# modem.net
KiCad netlist of a schematic drawn in Altium Designer
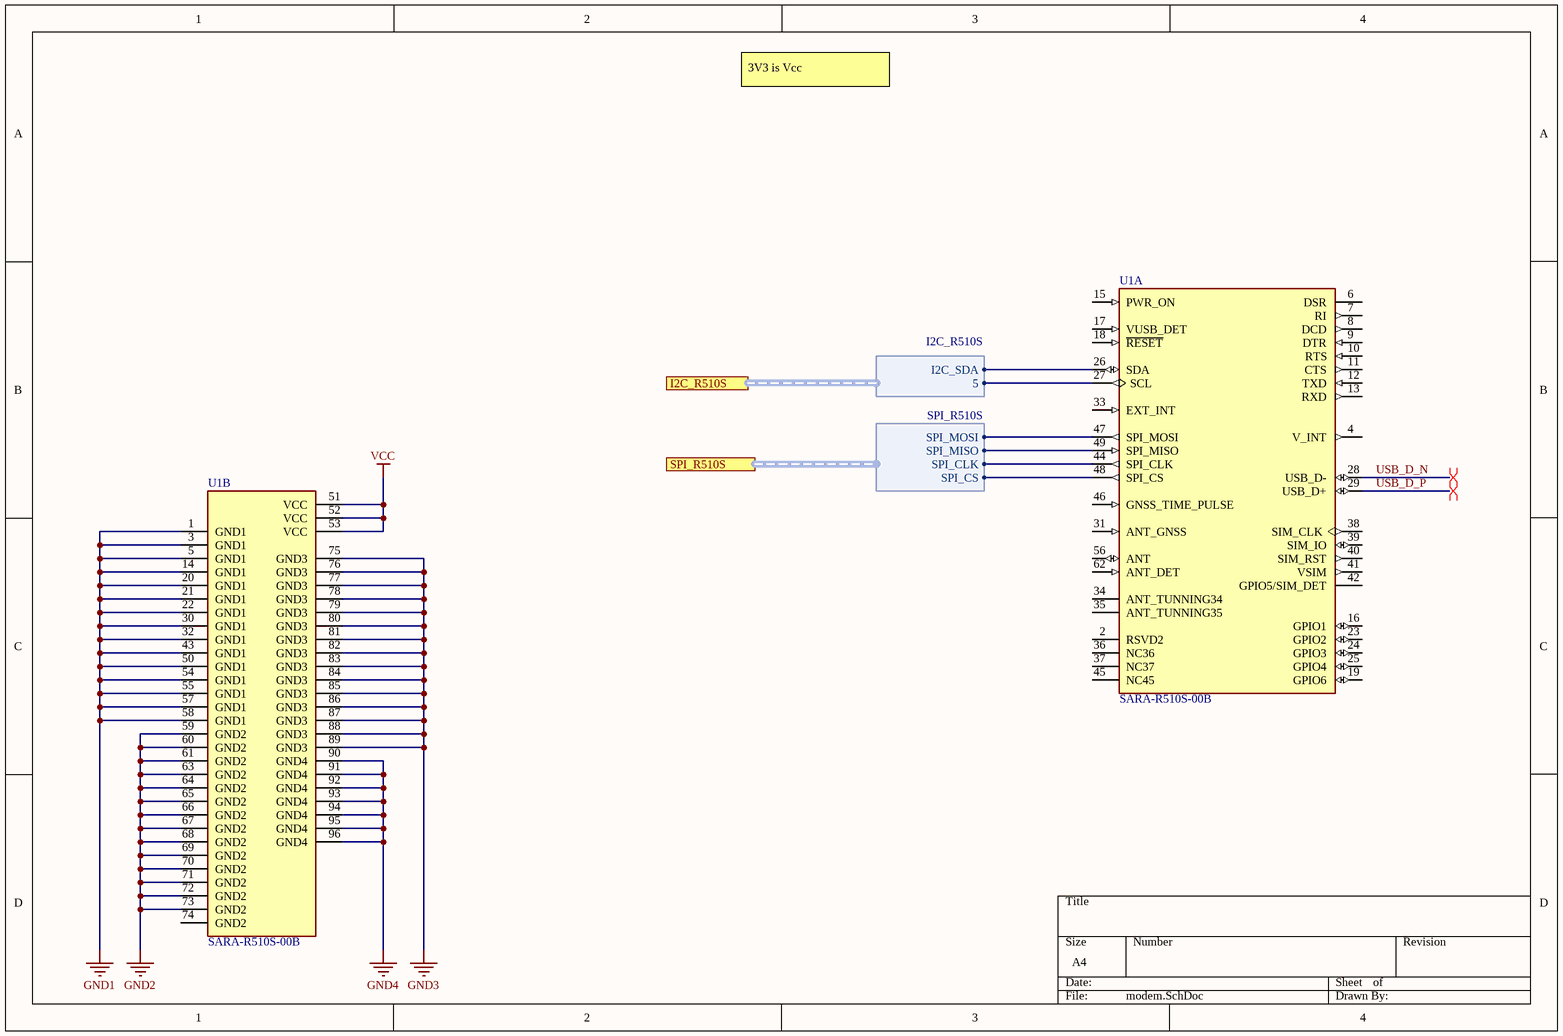
[diagram p0: modem.SchDoc]

(export (version "E")
  (design (tool "Eeschema 10.0.6"))
  (components
    (comp (ref "U1")
      (value "SARA-R510S-00B")
      (footprint "MODULE_SARA-R510S-00B - CORRECTED")
      (fields (field (name "MF") "U-Blox"))
      (libsource (lib "SARA-R510S-00B") (part "SARA-R510S-00B"))
    )
  )
  (nets
    (net (code "3") (name "/5") (class "Default")
      (node (ref "U1") (pin "27") (pinfunction "SCL_27") (pintype "output"))
    )
    (net (code "4") (name "/I2C_SDA") (class "Default")
      (node (ref "U1") (pin "26") (pinfunction "SDA_26") (pintype "bidirectional"))
    )
    (net (code "5") (name "/SPI_CLK") (class "Default")
      (node (ref "U1") (pin "44") (pinfunction "SPI_CLK_44") (pintype "output"))
    )
    (net (code "6") (name "/SPI_CS") (class "Default")
      (node (ref "U1") (pin "48") (pinfunction "SPI_CS_48") (pintype "output"))
    )
    (net (code "7") (name "/SPI_MISO") (class "Default")
      (node (ref "U1") (pin "49") (pinfunction "SPI_MISO_49") (pintype "input"))
    )
    (net (code "8") (name "/SPI_MOSI") (class "Default")
      (node (ref "U1") (pin "47") (pinfunction "SPI_MOSI_47") (pintype "output"))
    )
    (net (code "9") (name "/USB_D_N") (class "Default")
      (node (ref "U1") (pin "28") (pinfunction "USB_D-_28") (pintype "bidirectional"))
    )
    (net (code "10") (name "/USB_D_P") (class "Default")
      (node (ref "U1") (pin "29") (pinfunction "USB_D+_29") (pintype "bidirectional"))
    )
    (net (code "13") (name "GND1") (class "Default")
      (node (ref "U1") (pin "1") (pinfunction "GND1_1") (pintype "power_in"))
      (node (ref "U1") (pin "14") (pinfunction "GND1_14") (pintype "power_in"))
      (node (ref "U1") (pin "20") (pinfunction "GND1_20") (pintype "power_in"))
      (node (ref "U1") (pin "21") (pinfunction "GND1_21") (pintype "power_in"))
      (node (ref "U1") (pin "22") (pinfunction "GND1_22") (pintype "power_in"))
      (node (ref "U1") (pin "3") (pinfunction "GND1_3") (pintype "power_in"))
      (node (ref "U1") (pin "30") (pinfunction "GND1_30") (pintype "power_in"))
      (node (ref "U1") (pin "32") (pinfunction "GND1_32") (pintype "power_in"))
      (node (ref "U1") (pin "43") (pinfunction "GND1_43") (pintype "power_in"))
      (node (ref "U1") (pin "5") (pinfunction "GND1_5") (pintype "power_in"))
      (node (ref "U1") (pin "50") (pinfunction "GND1_50") (pintype "power_in"))
      (node (ref "U1") (pin "54") (pinfunction "GND1_54") (pintype "power_in"))
      (node (ref "U1") (pin "55") (pinfunction "GND1_55") (pintype "power_in"))
      (node (ref "U1") (pin "57") (pinfunction "GND1_57") (pintype "power_in"))
      (node (ref "U1") (pin "58") (pinfunction "GND1_58") (pintype "power_in"))
    )
    (net (code "14") (name "GND2") (class "Default")
      (node (ref "U1") (pin "59") (pinfunction "GND2_59") (pintype "power_in"))
      (node (ref "U1") (pin "60") (pinfunction "GND2_60") (pintype "power_in"))
      (node (ref "U1") (pin "61") (pinfunction "GND2_61") (pintype "power_in"))
      (node (ref "U1") (pin "63") (pinfunction "GND2_63") (pintype "power_in"))
      (node (ref "U1") (pin "64") (pinfunction "GND2_64") (pintype "power_in"))
      (node (ref "U1") (pin "65") (pinfunction "GND2_65") (pintype "power_in"))
      (node (ref "U1") (pin "66") (pinfunction "GND2_66") (pintype "power_in"))
      (node (ref "U1") (pin "67") (pinfunction "GND2_67") (pintype "power_in"))
      (node (ref "U1") (pin "68") (pinfunction "GND2_68") (pintype "power_in"))
      (node (ref "U1") (pin "69") (pinfunction "GND2_69") (pintype "power_in"))
      (node (ref "U1") (pin "70") (pinfunction "GND2_70") (pintype "power_in"))
      (node (ref "U1") (pin "71") (pinfunction "GND2_71") (pintype "power_in"))
      (node (ref "U1") (pin "72") (pinfunction "GND2_72") (pintype "power_in"))
      (node (ref "U1") (pin "73") (pinfunction "GND2_73") (pintype "power_in"))
    )
    (net (code "15") (name "GND3") (class "Default")
      (node (ref "U1") (pin "75") (pinfunction "GND3_75") (pintype "power_in"))
      (node (ref "U1") (pin "76") (pinfunction "GND3_76") (pintype "power_in"))
      (node (ref "U1") (pin "77") (pinfunction "GND3_77") (pintype "power_in"))
      (node (ref "U1") (pin "78") (pinfunction "GND3_78") (pintype "power_in"))
      (node (ref "U1") (pin "79") (pinfunction "GND3_79") (pintype "power_in"))
      (node (ref "U1") (pin "80") (pinfunction "GND3_80") (pintype "power_in"))
      (node (ref "U1") (pin "81") (pinfunction "GND3_81") (pintype "power_in"))
      (node (ref "U1") (pin "82") (pinfunction "GND3_82") (pintype "power_in"))
      (node (ref "U1") (pin "83") (pinfunction "GND3_83") (pintype "power_in"))
      (node (ref "U1") (pin "84") (pinfunction "GND3_84") (pintype "power_in"))
      (node (ref "U1") (pin "85") (pinfunction "GND3_85") (pintype "power_in"))
      (node (ref "U1") (pin "86") (pinfunction "GND3_86") (pintype "power_in"))
      (node (ref "U1") (pin "87") (pinfunction "GND3_87") (pintype "power_in"))
      (node (ref "U1") (pin "88") (pinfunction "GND3_88") (pintype "power_in"))
      (node (ref "U1") (pin "89") (pinfunction "GND3_89") (pintype "power_in"))
    )
    (net (code "16") (name "GND4") (class "Default")
      (node (ref "U1") (pin "90") (pinfunction "GND4_90") (pintype "power_in"))
      (node (ref "U1") (pin "91") (pinfunction "GND4_91") (pintype "power_in"))
      (node (ref "U1") (pin "92") (pinfunction "GND4_92") (pintype "power_in"))
      (node (ref "U1") (pin "93") (pinfunction "GND4_93") (pintype "power_in"))
      (node (ref "U1") (pin "94") (pinfunction "GND4_94") (pintype "power_in"))
      (node (ref "U1") (pin "95") (pinfunction "GND4_95") (pintype "power_in"))
      (node (ref "U1") (pin "96") (pinfunction "GND4_96") (pintype "power_in"))
    )
    (net (code "17") (name "VCC") (class "Default")
      (node (ref "U1") (pin "51") (pinfunction "VCC_51") (pintype "power_in"))
      (node (ref "U1") (pin "52") (pinfunction "VCC_52") (pintype "power_in"))
      (node (ref "U1") (pin "53") (pinfunction "VCC_53") (pintype "power_in"))
    )
    (net (code "18") (name "unconnected-(U1A-ANT-Pad56)") (class "Default")
      (node (ref "U1") (pin "56") (pinfunction "ANT_56") (pintype "bidirectional"))
    )
    (net (code "19") (name "unconnected-(U1A-ANT_DET-Pad62)") (class "Default")
      (node (ref "U1") (pin "62") (pinfunction "ANT_DET_62") (pintype "input"))
    )
    (net (code "20") (name "unconnected-(U1A-ANT_GNSS-Pad31)") (class "Default")
      (node (ref "U1") (pin "31") (pinfunction "ANT_GNSS_31") (pintype "input"))
    )
    (net (code "21") (name "unconnected-(U1A-ANT_TUNNING34-Pad34)") (class "Default")
      (node (ref "U1") (pin "34") (pinfunction "ANT_TUNNING34_34") (pintype "passive"))
    )
    (net (code "22") (name "unconnected-(U1A-ANT_TUNNING35-Pad35)") (class "Default")
      (node (ref "U1") (pin "35") (pinfunction "ANT_TUNNING35_35") (pintype "passive"))
    )
    (net (code "23") (name "unconnected-(U1A-CTS-Pad11)") (class "Default")
      (node (ref "U1") (pin "11") (pinfunction "CTS_11") (pintype "output"))
    )
    (net (code "24") (name "unconnected-(U1A-DCD-Pad8)") (class "Default")
      (node (ref "U1") (pin "8") (pinfunction "DCD_8") (pintype "output"))
    )
    (net (code "25") (name "unconnected-(U1A-DSR-Pad6)") (class "Default")
      (node (ref "U1") (pin "6") (pinfunction "DSR_6") (pintype "passive"))
    )
    (net (code "26") (name "unconnected-(U1A-DTR-Pad9)") (class "Default")
      (node (ref "U1") (pin "9") (pinfunction "DTR_9") (pintype "input"))
    )
    (net (code "27") (name "unconnected-(U1A-EXT_INT-Pad33)") (class "Default")
      (node (ref "U1") (pin "33") (pinfunction "EXT_INT_33") (pintype "input"))
    )
    (net (code "28") (name "unconnected-(U1A-GNSS_TIME_PULSE-Pad46)") (class "Default")
      (node (ref "U1") (pin "46") (pinfunction "GNSS_TIME_PULSE_46") (pintype "input"))
    )
    (net (code "29") (name "unconnected-(U1A-GPIO1-Pad16)") (class "Default")
      (node (ref "U1") (pin "16") (pinfunction "GPIO1_16") (pintype "bidirectional"))
    )
    (net (code "30") (name "unconnected-(U1A-GPIO2-Pad23)") (class "Default")
      (node (ref "U1") (pin "23") (pinfunction "GPIO2_23") (pintype "bidirectional"))
    )
    (net (code "31") (name "unconnected-(U1A-GPIO3-Pad24)") (class "Default")
      (node (ref "U1") (pin "24") (pinfunction "GPIO3_24") (pintype "bidirectional"))
    )
    (net (code "32") (name "unconnected-(U1A-GPIO4-Pad25)") (class "Default")
      (node (ref "U1") (pin "25") (pinfunction "GPIO4_25") (pintype "bidirectional"))
    )
    (net (code "33") (name "unconnected-(U1A-GPIO5{slash}SIM_DET-Pad42)") (class "Default")
      (node (ref "U1") (pin "42") (pinfunction "GPIO5/SIM_DET_42") (pintype "passive"))
    )
    (net (code "34") (name "unconnected-(U1A-GPIO6-Pad19)") (class "Default")
      (node (ref "U1") (pin "19") (pinfunction "GPIO6_19") (pintype "bidirectional"))
    )
    (net (code "35") (name "unconnected-(U1A-NC36-Pad36)") (class "Default")
      (node (ref "U1") (pin "36") (pinfunction "NC36_36") (pintype "passive"))
    )
    (net (code "36") (name "unconnected-(U1A-NC37-Pad37)") (class "Default")
      (node (ref "U1") (pin "37") (pinfunction "NC37_37") (pintype "passive"))
    )
    (net (code "37") (name "unconnected-(U1A-NC45-Pad45)") (class "Default")
      (node (ref "U1") (pin "45") (pinfunction "NC45_45") (pintype "passive"))
    )
    (net (code "38") (name "unconnected-(U1A-PWR_ON-Pad15)") (class "Default")
      (node (ref "U1") (pin "15") (pinfunction "PWR_ON_15") (pintype "input"))
    )
    (net (code "39") (name "unconnected-(U1A-RI-Pad7)") (class "Default")
      (node (ref "U1") (pin "7") (pinfunction "RI_7") (pintype "output"))
    )
    (net (code "40") (name "unconnected-(U1A-RSVD2-Pad2)") (class "Default")
      (node (ref "U1") (pin "2") (pinfunction "RSVD2_2") (pintype "passive"))
    )
    (net (code "41") (name "unconnected-(U1A-RTS-Pad10)") (class "Default")
      (node (ref "U1") (pin "10") (pinfunction "RTS_10") (pintype "input"))
    )
    (net (code "42") (name "unconnected-(U1A-RXD-Pad13)") (class "Default")
      (node (ref "U1") (pin "13") (pinfunction "RXD_13") (pintype "output"))
    )
    (net (code "43") (name "unconnected-(U1A-SIM_CLK-Pad38)") (class "Default")
      (node (ref "U1") (pin "38") (pinfunction "SIM_CLK_38") (pintype "output"))
    )
    (net (code "44") (name "unconnected-(U1A-SIM_IO-Pad39)") (class "Default")
      (node (ref "U1") (pin "39") (pinfunction "SIM_IO_39") (pintype "bidirectional"))
    )
    (net (code "45") (name "unconnected-(U1A-SIM_RST-Pad40)") (class "Default")
      (node (ref "U1") (pin "40") (pinfunction "SIM_RST_40") (pintype "output"))
    )
    (net (code "46") (name "unconnected-(U1A-TXD-Pad12)") (class "Default")
      (node (ref "U1") (pin "12") (pinfunction "TXD_12") (pintype "input"))
    )
    (net (code "47") (name "unconnected-(U1A-VSIM-Pad41)") (class "Default")
      (node (ref "U1") (pin "41") (pinfunction "VSIM_41") (pintype "output"))
    )
    (net (code "48") (name "unconnected-(U1A-VUSB_DET-Pad17)") (class "Default")
      (node (ref "U1") (pin "17") (pinfunction "VUSB_DET_17") (pintype "input"))
    )
    (net (code "49") (name "unconnected-(U1A-V_INT-Pad4)") (class "Default")
      (node (ref "U1") (pin "4") (pinfunction "V_INT_4") (pintype "output"))
    )
    (net (code "50") (name "unconnected-(U1A-~{RESET}-Pad18)") (class "Default")
      (node (ref "U1") (pin "18") (pinfunction "~{RESET}_18") (pintype "input"))
    )
    (net (code "51") (name "unconnected-(U1B-GND2-Pad74)") (class "Default")
      (node (ref "U1") (pin "74") (pinfunction "GND2_74") (pintype "power_in"))
    )
  )
)
